# CAPT-B1-02_Cap_Touch_Matrix_Shield.net
KiCad netlist of a schematic drawn in EAGLE
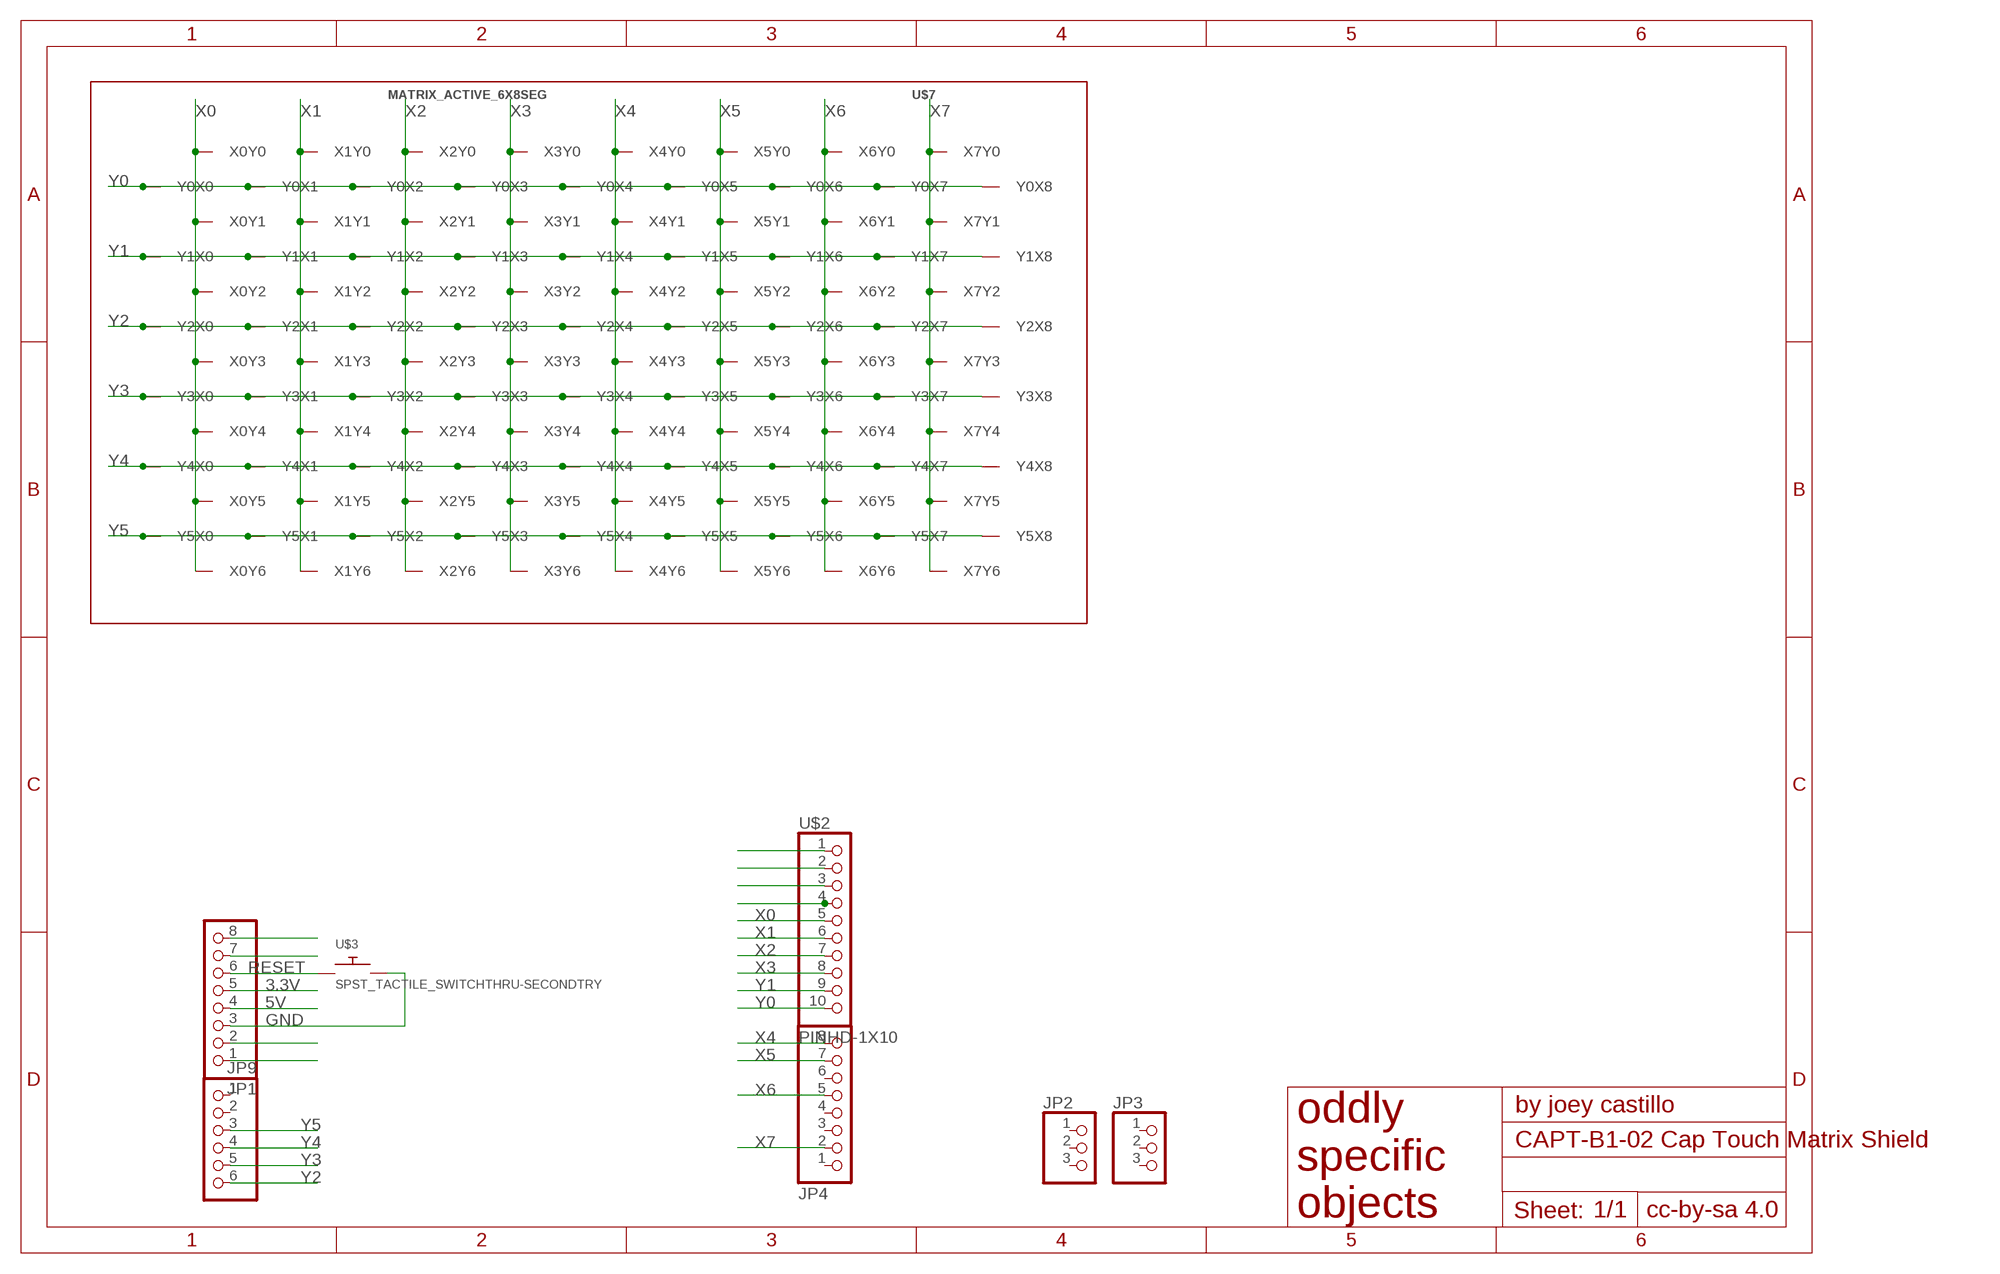
[diagram p0: schematic, sheet 1]

(export (version "E")
  (design (tool "Eeschema 10.0.6"))
  (components
    (comp (ref "JP1")
      (value "PINHD-1X8CLEANBIG")
      (footprint "eagle-import:1X08-CLEANBIG")
      (libsource (lib "eagle-import") (part "PINHD-1X8CLEANBIG"))
    )
    (comp (ref "JP2")
      (value "PINHD-1X3CB")
      (footprint "eagle-import:1X03-CLEANBIG")
      (libsource (lib "eagle-import") (part "PINHD-1X3CB"))
    )
    (comp (ref "JP3")
      (value "PINHD-1X3CB")
      (footprint "eagle-import:1X03-CLEANBIG")
      (libsource (lib "eagle-import") (part "PINHD-1X3CB"))
    )
    (comp (ref "JP4")
      (value "PINHD-1X8CLEANBIG")
      (footprint "eagle-import:1X08-CLEANBIG")
      (libsource (lib "eagle-import") (part "PINHD-1X8CLEANBIG"))
    )
    (comp (ref "JP9")
      (value "PINHD-1X6CB")
      (footprint "eagle-import:1X06-CLEANBIG")
      (libsource (lib "eagle-import") (part "PINHD-1X6CB"))
    )
    (comp (ref "U$2")
      (value "PINHD-1X10")
      (footprint "eagle-import:1X10-BIG")
      (libsource (lib "eagle-import") (part "PINHD-1X10"))
    )
    (comp (ref "U$3")
      (value "SPST_TACTILE_SWITCHTHRU-SECONDTRY")
      (footprint "eagle-import:MJTP1250-TRY2")
      (libsource (lib "eagle-import") (part "SPST_TACTILE_SWITCHTHRU-SECONDTRY"))
    )
    (comp (ref "U$7")
      (value "MATRIX_ACTIVE_6X8SEG")
      (footprint "eagle-import:MATRIX_ACTIVE_6X8SEG_6MM")
      (libsource (lib "eagle-import") (part "MATRIX_ACTIVE_6X8SEG"))
    )
  )
  (nets
    (net (code "1") (name "/3.3V") (class "Default")
      (node (ref "JP1") (pin "5") (pinfunction "5_5") (pintype "passive"))
    )
    (net (code "2") (name "/5V") (class "Default")
      (node (ref "JP1") (pin "4") (pinfunction "4_4") (pintype "passive"))
    )
    (net (code "3") (name "/GND") (class "Default")
      (node (ref "JP1") (pin "3") (pinfunction "3_3") (pintype "passive"))
      (node (ref "U$3") (pin "P$2") (pinfunction "P$2_P$2") (pintype "passive"))
    )
    (net (code "4") (name "/RESET") (class "Default")
      (node (ref "JP1") (pin "6") (pinfunction "6_6") (pintype "passive"))
      (node (ref "U$3") (pin "P$1") (pinfunction "P$1_P$1") (pintype "passive"))
    )
    (net (code "5") (name "/X0") (class "Default")
      (node (ref "U$2") (pin "5") (pinfunction "5_5") (pintype "passive"))
      (node (ref "U$7") (pin "X0Y0") (pinfunction "X0Y0_X0Y0") (pintype "passive"))
      (node (ref "U$7") (pin "X0Y1") (pinfunction "X0Y1_X0Y1") (pintype "passive"))
      (node (ref "U$7") (pin "X0Y2") (pinfunction "X0Y2_X0Y2") (pintype "passive"))
      (node (ref "U$7") (pin "X0Y3") (pinfunction "X0Y3_X0Y3") (pintype "passive"))
      (node (ref "U$7") (pin "X0Y4") (pinfunction "X0Y4_X0Y4") (pintype "passive"))
      (node (ref "U$7") (pin "X0Y5") (pinfunction "X0Y5_X0Y5") (pintype "passive"))
      (node (ref "U$7") (pin "X0Y6") (pinfunction "X0Y6_X0Y6") (pintype "passive"))
    )
    (net (code "6") (name "/X1") (class "Default")
      (node (ref "U$2") (pin "6") (pinfunction "6_6") (pintype "passive"))
      (node (ref "U$7") (pin "X1Y0") (pinfunction "X1Y0_X1Y0") (pintype "passive"))
      (node (ref "U$7") (pin "X1Y1") (pinfunction "X1Y1_X1Y1") (pintype "passive"))
      (node (ref "U$7") (pin "X1Y2") (pinfunction "X1Y2_X1Y2") (pintype "passive"))
      (node (ref "U$7") (pin "X1Y3") (pinfunction "X1Y3_X1Y3") (pintype "passive"))
      (node (ref "U$7") (pin "X1Y4") (pinfunction "X1Y4_X1Y4") (pintype "passive"))
      (node (ref "U$7") (pin "X1Y5") (pinfunction "X1Y5_X1Y5") (pintype "passive"))
      (node (ref "U$7") (pin "X1Y6") (pinfunction "X1Y6_X1Y6") (pintype "passive"))
    )
    (net (code "7") (name "/X2") (class "Default")
      (node (ref "U$2") (pin "7") (pinfunction "7_7") (pintype "passive"))
      (node (ref "U$7") (pin "X2Y0") (pinfunction "X2Y0_X2Y0") (pintype "passive"))
      (node (ref "U$7") (pin "X2Y1") (pinfunction "X2Y1_X2Y1") (pintype "passive"))
      (node (ref "U$7") (pin "X2Y2") (pinfunction "X2Y2_X2Y2") (pintype "passive"))
      (node (ref "U$7") (pin "X2Y3") (pinfunction "X2Y3_X2Y3") (pintype "passive"))
      (node (ref "U$7") (pin "X2Y4") (pinfunction "X2Y4_X2Y4") (pintype "passive"))
      (node (ref "U$7") (pin "X2Y5") (pinfunction "X2Y5_X2Y5") (pintype "passive"))
      (node (ref "U$7") (pin "X2Y6") (pinfunction "X2Y6_X2Y6") (pintype "passive"))
    )
    (net (code "8") (name "/X3") (class "Default")
      (node (ref "U$2") (pin "8") (pinfunction "8_8") (pintype "passive"))
      (node (ref "U$7") (pin "X3Y0") (pinfunction "X3Y0_X3Y0") (pintype "passive"))
      (node (ref "U$7") (pin "X3Y1") (pinfunction "X3Y1_X3Y1") (pintype "passive"))
      (node (ref "U$7") (pin "X3Y2") (pinfunction "X3Y2_X3Y2") (pintype "passive"))
      (node (ref "U$7") (pin "X3Y3") (pinfunction "X3Y3_X3Y3") (pintype "passive"))
      (node (ref "U$7") (pin "X3Y4") (pinfunction "X3Y4_X3Y4") (pintype "passive"))
      (node (ref "U$7") (pin "X3Y5") (pinfunction "X3Y5_X3Y5") (pintype "passive"))
      (node (ref "U$7") (pin "X3Y6") (pinfunction "X3Y6_X3Y6") (pintype "passive"))
    )
    (net (code "9") (name "/X4") (class "Default")
      (node (ref "JP4") (pin "8") (pinfunction "8_8") (pintype "passive"))
      (node (ref "U$7") (pin "X4Y0") (pinfunction "X4Y0_X4Y0") (pintype "passive"))
      (node (ref "U$7") (pin "X4Y1") (pinfunction "X4Y1_X4Y1") (pintype "passive"))
      (node (ref "U$7") (pin "X4Y2") (pinfunction "X4Y2_X4Y2") (pintype "passive"))
      (node (ref "U$7") (pin "X4Y3") (pinfunction "X4Y3_X4Y3") (pintype "passive"))
      (node (ref "U$7") (pin "X4Y4") (pinfunction "X4Y4_X4Y4") (pintype "passive"))
      (node (ref "U$7") (pin "X4Y5") (pinfunction "X4Y5_X4Y5") (pintype "passive"))
      (node (ref "U$7") (pin "X4Y6") (pinfunction "X4Y6_X4Y6") (pintype "passive"))
    )
    (net (code "10") (name "/X5") (class "Default")
      (node (ref "JP4") (pin "7") (pinfunction "7_7") (pintype "passive"))
      (node (ref "U$7") (pin "X5Y0") (pinfunction "X5Y0_X5Y0") (pintype "passive"))
      (node (ref "U$7") (pin "X5Y1") (pinfunction "X5Y1_X5Y1") (pintype "passive"))
      (node (ref "U$7") (pin "X5Y2") (pinfunction "X5Y2_X5Y2") (pintype "passive"))
      (node (ref "U$7") (pin "X5Y3") (pinfunction "X5Y3_X5Y3") (pintype "passive"))
      (node (ref "U$7") (pin "X5Y4") (pinfunction "X5Y4_X5Y4") (pintype "passive"))
      (node (ref "U$7") (pin "X5Y5") (pinfunction "X5Y5_X5Y5") (pintype "passive"))
      (node (ref "U$7") (pin "X5Y6") (pinfunction "X5Y6_X5Y6") (pintype "passive"))
    )
    (net (code "11") (name "/X6") (class "Default")
      (node (ref "JP4") (pin "5") (pinfunction "5_5") (pintype "passive"))
      (node (ref "U$7") (pin "X6Y0") (pinfunction "X6Y0_X6Y0") (pintype "passive"))
      (node (ref "U$7") (pin "X6Y1") (pinfunction "X6Y1_X6Y1") (pintype "passive"))
      (node (ref "U$7") (pin "X6Y2") (pinfunction "X6Y2_X6Y2") (pintype "passive"))
      (node (ref "U$7") (pin "X6Y3") (pinfunction "X6Y3_X6Y3") (pintype "passive"))
      (node (ref "U$7") (pin "X6Y4") (pinfunction "X6Y4_X6Y4") (pintype "passive"))
      (node (ref "U$7") (pin "X6Y5") (pinfunction "X6Y5_X6Y5") (pintype "passive"))
      (node (ref "U$7") (pin "X6Y6") (pinfunction "X6Y6_X6Y6") (pintype "passive"))
    )
    (net (code "12") (name "/X7") (class "Default")
      (node (ref "JP4") (pin "2") (pinfunction "2_2") (pintype "passive"))
      (node (ref "U$7") (pin "X7Y0") (pinfunction "X7Y0_X7Y0") (pintype "passive"))
      (node (ref "U$7") (pin "X7Y1") (pinfunction "X7Y1_X7Y1") (pintype "passive"))
      (node (ref "U$7") (pin "X7Y2") (pinfunction "X7Y2_X7Y2") (pintype "passive"))
      (node (ref "U$7") (pin "X7Y3") (pinfunction "X7Y3_X7Y3") (pintype "passive"))
      (node (ref "U$7") (pin "X7Y4") (pinfunction "X7Y4_X7Y4") (pintype "passive"))
      (node (ref "U$7") (pin "X7Y5") (pinfunction "X7Y5_X7Y5") (pintype "passive"))
      (node (ref "U$7") (pin "X7Y6") (pinfunction "X7Y6_X7Y6") (pintype "passive"))
    )
    (net (code "13") (name "/Y0") (class "Default")
      (node (ref "U$2") (pin "10") (pinfunction "10_10") (pintype "passive"))
      (node (ref "U$7") (pin "Y0X0") (pinfunction "Y0X0_Y0X0") (pintype "passive"))
      (node (ref "U$7") (pin "Y0X1") (pinfunction "Y0X1_Y0X1") (pintype "passive"))
      (node (ref "U$7") (pin "Y0X2") (pinfunction "Y0X2_Y0X2") (pintype "passive"))
      (node (ref "U$7") (pin "Y0X3") (pinfunction "Y0X3_Y0X3") (pintype "passive"))
      (node (ref "U$7") (pin "Y0X4") (pinfunction "Y0X4_Y0X4") (pintype "passive"))
      (node (ref "U$7") (pin "Y0X5") (pinfunction "Y0X5_Y0X5") (pintype "passive"))
      (node (ref "U$7") (pin "Y0X6") (pinfunction "Y0X6_Y0X6") (pintype "passive"))
      (node (ref "U$7") (pin "Y0X7") (pinfunction "Y0X7_Y0X7") (pintype "passive"))
      (node (ref "U$7") (pin "Y0X8") (pinfunction "Y0X8_Y0X8") (pintype "passive"))
    )
    (net (code "14") (name "/Y1") (class "Default")
      (node (ref "U$2") (pin "9") (pinfunction "9_9") (pintype "passive"))
      (node (ref "U$7") (pin "Y1X0") (pinfunction "Y1X0_Y1X0") (pintype "passive"))
      (node (ref "U$7") (pin "Y1X1") (pinfunction "Y1X1_Y1X1") (pintype "passive"))
      (node (ref "U$7") (pin "Y1X2") (pinfunction "Y1X2_Y1X2") (pintype "passive"))
      (node (ref "U$7") (pin "Y1X3") (pinfunction "Y1X3_Y1X3") (pintype "passive"))
      (node (ref "U$7") (pin "Y1X4") (pinfunction "Y1X4_Y1X4") (pintype "passive"))
      (node (ref "U$7") (pin "Y1X5") (pinfunction "Y1X5_Y1X5") (pintype "passive"))
      (node (ref "U$7") (pin "Y1X6") (pinfunction "Y1X6_Y1X6") (pintype "passive"))
      (node (ref "U$7") (pin "Y1X7") (pinfunction "Y1X7_Y1X7") (pintype "passive"))
      (node (ref "U$7") (pin "Y1X8") (pinfunction "Y1X8_Y1X8") (pintype "passive"))
    )
    (net (code "15") (name "/Y2") (class "Default")
      (node (ref "JP9") (pin "6") (pinfunction "6_6") (pintype "passive"))
      (node (ref "U$7") (pin "Y2X0") (pinfunction "Y2X0_Y2X0") (pintype "passive"))
      (node (ref "U$7") (pin "Y2X1") (pinfunction "Y2X1_Y2X1") (pintype "passive"))
      (node (ref "U$7") (pin "Y2X2") (pinfunction "Y2X2_Y2X2") (pintype "passive"))
      (node (ref "U$7") (pin "Y2X3") (pinfunction "Y2X3_Y2X3") (pintype "passive"))
      (node (ref "U$7") (pin "Y2X4") (pinfunction "Y2X4_Y2X4") (pintype "passive"))
      (node (ref "U$7") (pin "Y2X5") (pinfunction "Y2X5_Y2X5") (pintype "passive"))
      (node (ref "U$7") (pin "Y2X6") (pinfunction "Y2X6_Y2X6") (pintype "passive"))
      (node (ref "U$7") (pin "Y2X7") (pinfunction "Y2X7_Y2X7") (pintype "passive"))
      (node (ref "U$7") (pin "Y2X8") (pinfunction "Y2X8_Y2X8") (pintype "passive"))
    )
    (net (code "16") (name "/Y3") (class "Default")
      (node (ref "JP9") (pin "5") (pinfunction "5_5") (pintype "passive"))
      (node (ref "U$7") (pin "Y3X0") (pinfunction "Y3X0_Y3X0") (pintype "passive"))
      (node (ref "U$7") (pin "Y3X1") (pinfunction "Y3X1_Y3X1") (pintype "passive"))
      (node (ref "U$7") (pin "Y3X2") (pinfunction "Y3X2_Y3X2") (pintype "passive"))
      (node (ref "U$7") (pin "Y3X3") (pinfunction "Y3X3_Y3X3") (pintype "passive"))
      (node (ref "U$7") (pin "Y3X4") (pinfunction "Y3X4_Y3X4") (pintype "passive"))
      (node (ref "U$7") (pin "Y3X5") (pinfunction "Y3X5_Y3X5") (pintype "passive"))
      (node (ref "U$7") (pin "Y3X6") (pinfunction "Y3X6_Y3X6") (pintype "passive"))
      (node (ref "U$7") (pin "Y3X7") (pinfunction "Y3X7_Y3X7") (pintype "passive"))
      (node (ref "U$7") (pin "Y3X8") (pinfunction "Y3X8_Y3X8") (pintype "passive"))
    )
    (net (code "17") (name "/Y4") (class "Default")
      (node (ref "JP9") (pin "4") (pinfunction "4_4") (pintype "passive"))
      (node (ref "U$7") (pin "Y4X0") (pinfunction "Y4X0_Y4X0") (pintype "passive"))
      (node (ref "U$7") (pin "Y4X1") (pinfunction "Y4X1_Y4X1") (pintype "passive"))
      (node (ref "U$7") (pin "Y4X2") (pinfunction "Y4X2_Y4X2") (pintype "passive"))
      (node (ref "U$7") (pin "Y4X3") (pinfunction "Y4X3_Y4X3") (pintype "passive"))
      (node (ref "U$7") (pin "Y4X4") (pinfunction "Y4X4_Y4X4") (pintype "passive"))
      (node (ref "U$7") (pin "Y4X5") (pinfunction "Y4X5_Y4X5") (pintype "passive"))
      (node (ref "U$7") (pin "Y4X6") (pinfunction "Y4X6_Y4X6") (pintype "passive"))
      (node (ref "U$7") (pin "Y4X7") (pinfunction "Y4X7_Y4X7") (pintype "passive"))
      (node (ref "U$7") (pin "Y4X8") (pinfunction "Y4X8_Y4X8") (pintype "passive"))
    )
    (net (code "18") (name "/Y5") (class "Default")
      (node (ref "JP9") (pin "3") (pinfunction "3_3") (pintype "passive"))
      (node (ref "U$7") (pin "Y5X0") (pinfunction "Y5X0_Y5X0") (pintype "passive"))
      (node (ref "U$7") (pin "Y5X1") (pinfunction "Y5X1_Y5X1") (pintype "passive"))
      (node (ref "U$7") (pin "Y5X2") (pinfunction "Y5X2_Y5X2") (pintype "passive"))
      (node (ref "U$7") (pin "Y5X3") (pinfunction "Y5X3_Y5X3") (pintype "passive"))
      (node (ref "U$7") (pin "Y5X4") (pinfunction "Y5X4_Y5X4") (pintype "passive"))
      (node (ref "U$7") (pin "Y5X5") (pinfunction "Y5X5_Y5X5") (pintype "passive"))
      (node (ref "U$7") (pin "Y5X6") (pinfunction "Y5X6_Y5X6") (pintype "passive"))
      (node (ref "U$7") (pin "Y5X7") (pinfunction "Y5X7_Y5X7") (pintype "passive"))
      (node (ref "U$7") (pin "Y5X8") (pinfunction "Y5X8_Y5X8") (pintype "passive"))
    )
    (net (code "19") (name "unconnected-(JP1-Pad1)") (class "Default")
      (node (ref "JP1") (pin "1") (pinfunction "1_1") (pintype "passive"))
    )
    (net (code "20") (name "unconnected-(JP1-Pad2)") (class "Default")
      (node (ref "JP1") (pin "2") (pinfunction "2_2") (pintype "passive"))
    )
    (net (code "21") (name "unconnected-(JP1-Pad7)") (class "Default")
      (node (ref "JP1") (pin "7") (pinfunction "7_7") (pintype "passive"))
    )
    (net (code "22") (name "unconnected-(JP1-Pad8)") (class "Default")
      (node (ref "JP1") (pin "8") (pinfunction "8_8") (pintype "passive"))
    )
    (net (code "23") (name "unconnected-(JP2-Pad1)") (class "Default")
      (node (ref "JP2") (pin "1") (pinfunction "1_1") (pintype "passive"))
    )
    (net (code "24") (name "unconnected-(JP2-Pad2)") (class "Default")
      (node (ref "JP2") (pin "2") (pinfunction "2_2") (pintype "passive"))
    )
    (net (code "25") (name "unconnected-(JP2-Pad3)") (class "Default")
      (node (ref "JP2") (pin "3") (pinfunction "3_3") (pintype "passive"))
    )
    (net (code "26") (name "unconnected-(JP3-Pad1)") (class "Default")
      (node (ref "JP3") (pin "1") (pinfunction "1_1") (pintype "passive"))
    )
    (net (code "27") (name "unconnected-(JP3-Pad2)") (class "Default")
      (node (ref "JP3") (pin "2") (pinfunction "2_2") (pintype "passive"))
    )
    (net (code "28") (name "unconnected-(JP3-Pad3)") (class "Default")
      (node (ref "JP3") (pin "3") (pinfunction "3_3") (pintype "passive"))
    )
    (net (code "29") (name "unconnected-(JP4-Pad1)") (class "Default")
      (node (ref "JP4") (pin "1") (pinfunction "1_1") (pintype "passive"))
    )
    (net (code "30") (name "unconnected-(JP4-Pad3)") (class "Default")
      (node (ref "JP4") (pin "3") (pinfunction "3_3") (pintype "passive"))
    )
    (net (code "31") (name "unconnected-(JP4-Pad4)") (class "Default")
      (node (ref "JP4") (pin "4") (pinfunction "4_4") (pintype "passive"))
    )
    (net (code "32") (name "unconnected-(JP4-Pad6)") (class "Default")
      (node (ref "JP4") (pin "6") (pinfunction "6_6") (pintype "passive"))
    )
    (net (code "33") (name "unconnected-(JP9-Pad1)") (class "Default")
      (node (ref "JP9") (pin "1") (pinfunction "1_1") (pintype "passive"))
    )
    (net (code "34") (name "unconnected-(JP9-Pad2)") (class "Default")
      (node (ref "JP9") (pin "2") (pinfunction "2_2") (pintype "passive"))
    )
    (net (code "35") (name "unconnected-(U$2-Pad1)") (class "Default")
      (node (ref "U$2") (pin "1") (pinfunction "1_1") (pintype "passive"))
    )
    (net (code "36") (name "unconnected-(U$2-Pad2)") (class "Default")
      (node (ref "U$2") (pin "2") (pinfunction "2_2") (pintype "passive"))
    )
    (net (code "37") (name "unconnected-(U$2-Pad3)") (class "Default")
      (node (ref "U$2") (pin "3") (pinfunction "3_3") (pintype "passive"))
    )
    (net (code "38") (name "unconnected-(U$2-Pad4)") (class "Default")
      (node (ref "U$2") (pin "4") (pinfunction "4_4") (pintype "passive"))
    )
  )
)
